# 1-Schematic_testflight2_pcb.net
KiCad netlist of a schematic drawn in EasyEDA
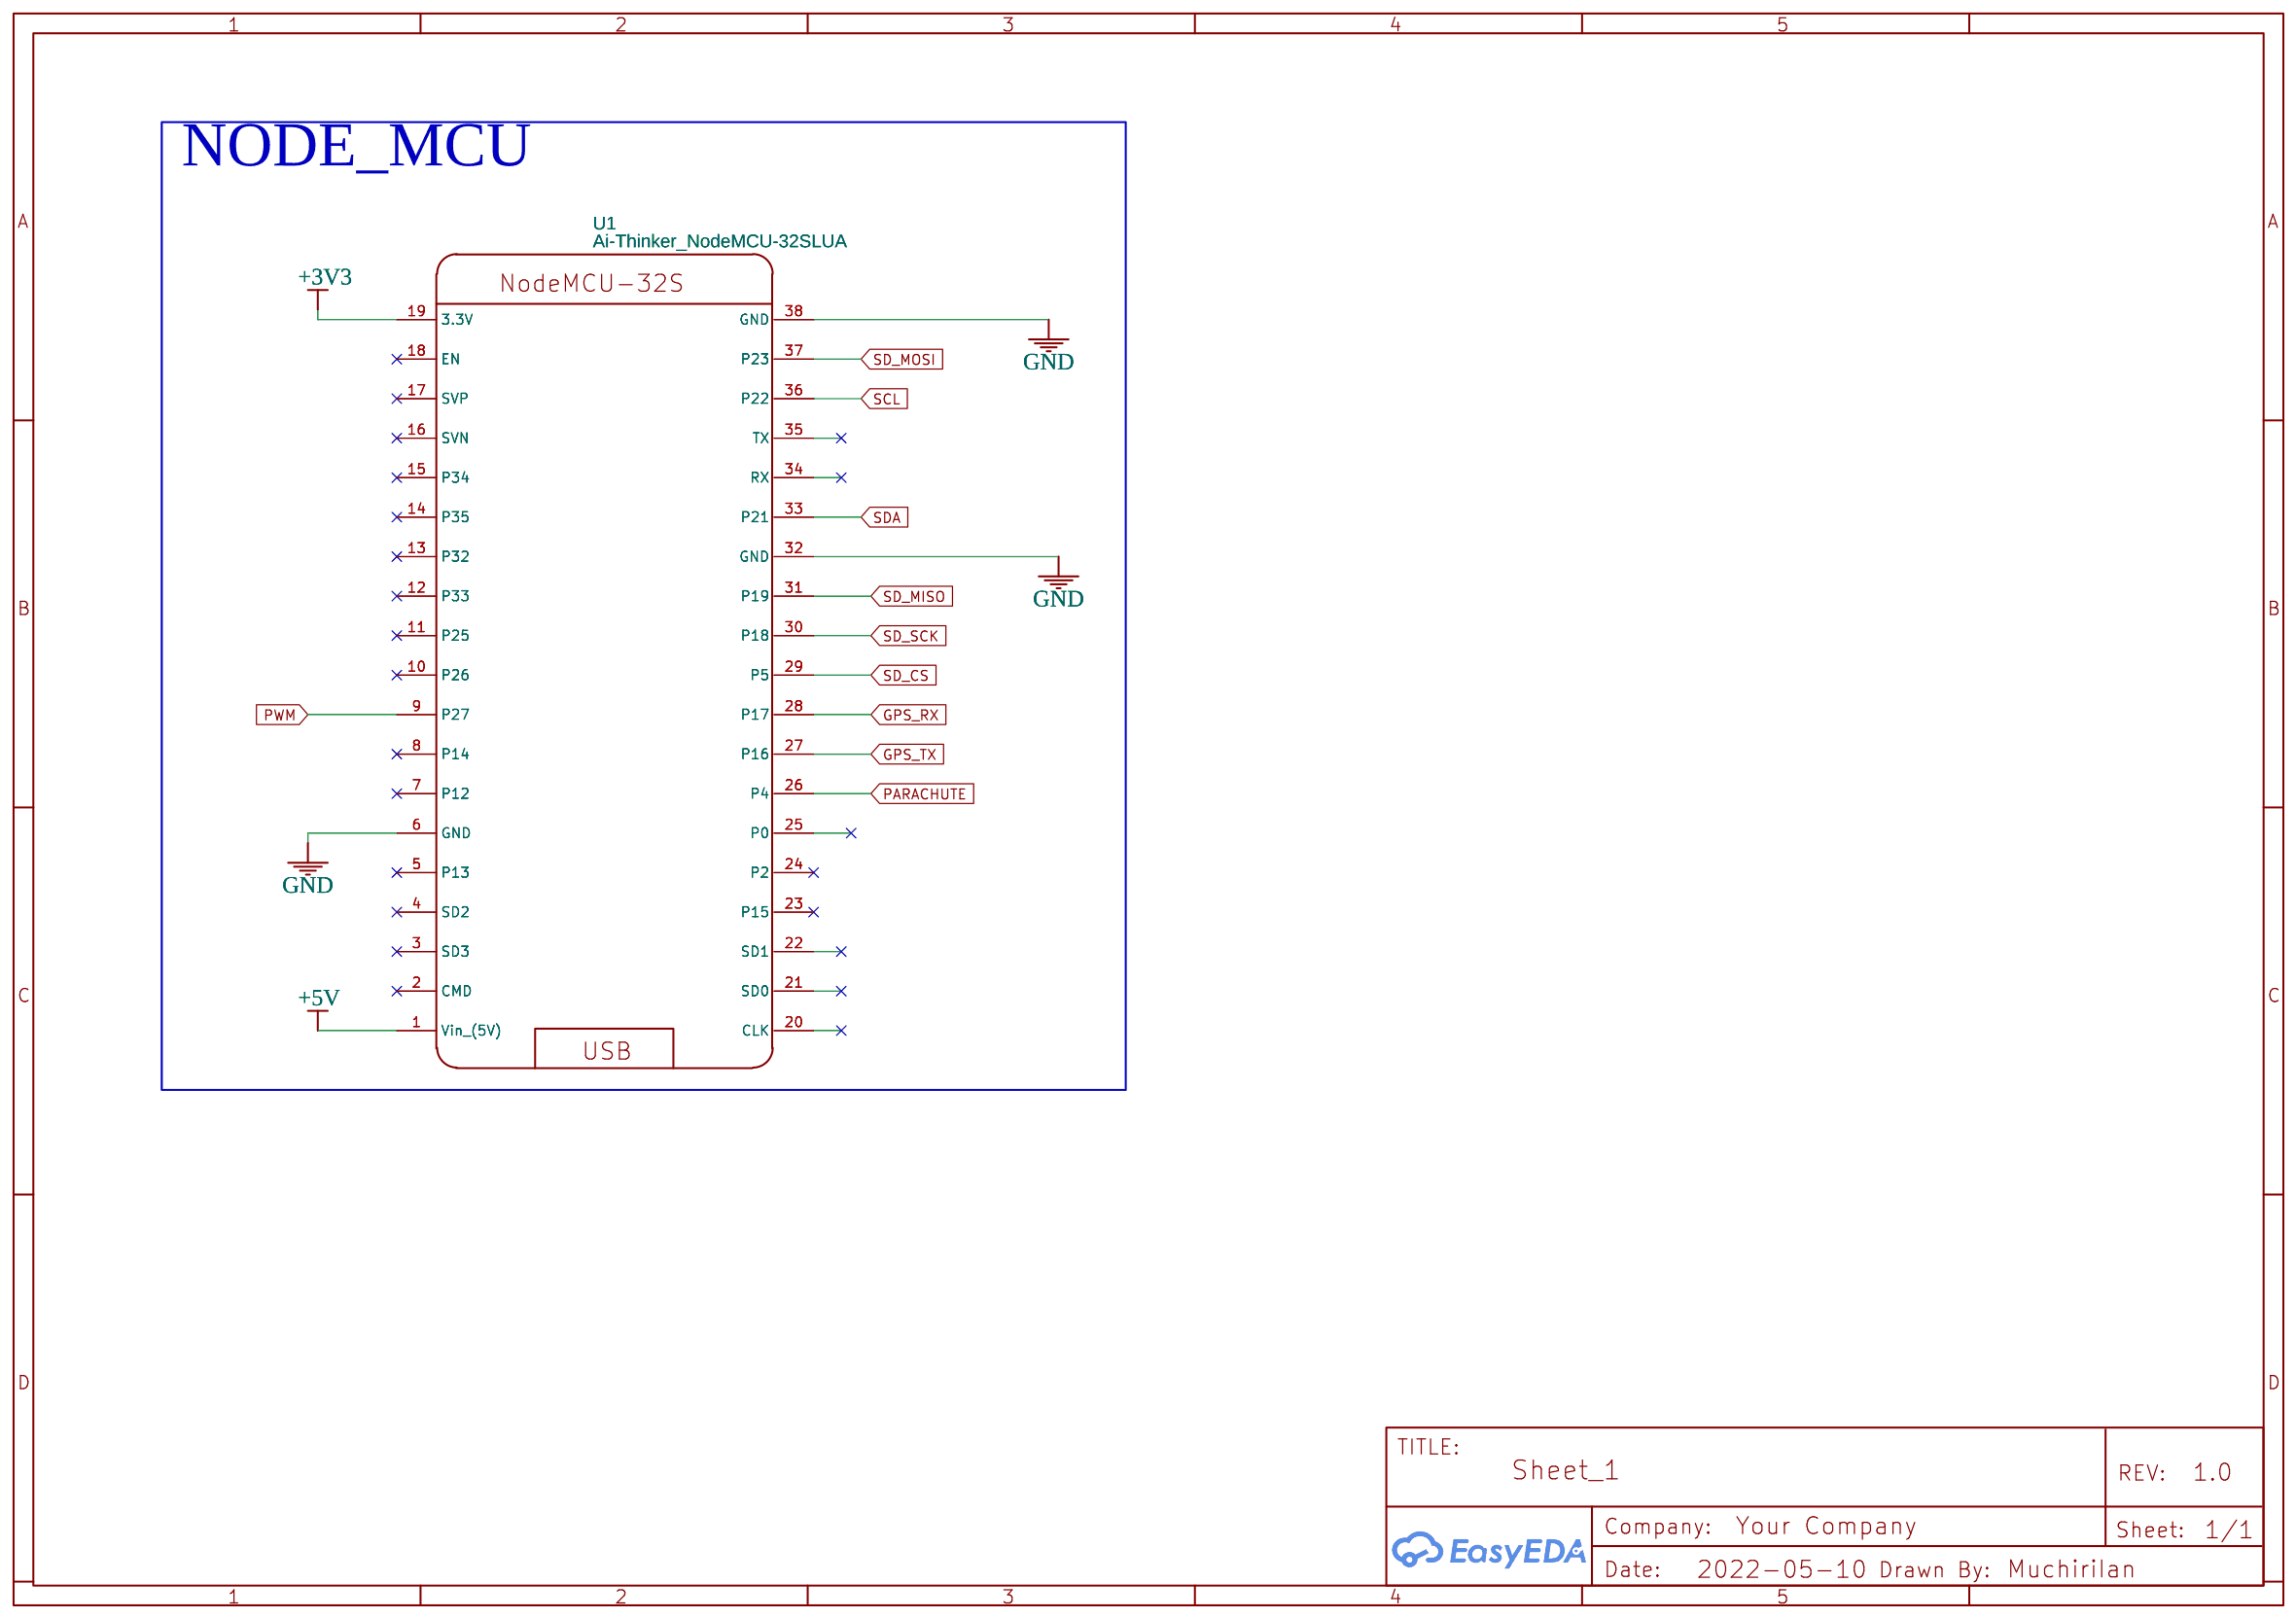
[diagram p0: Sheet_1]
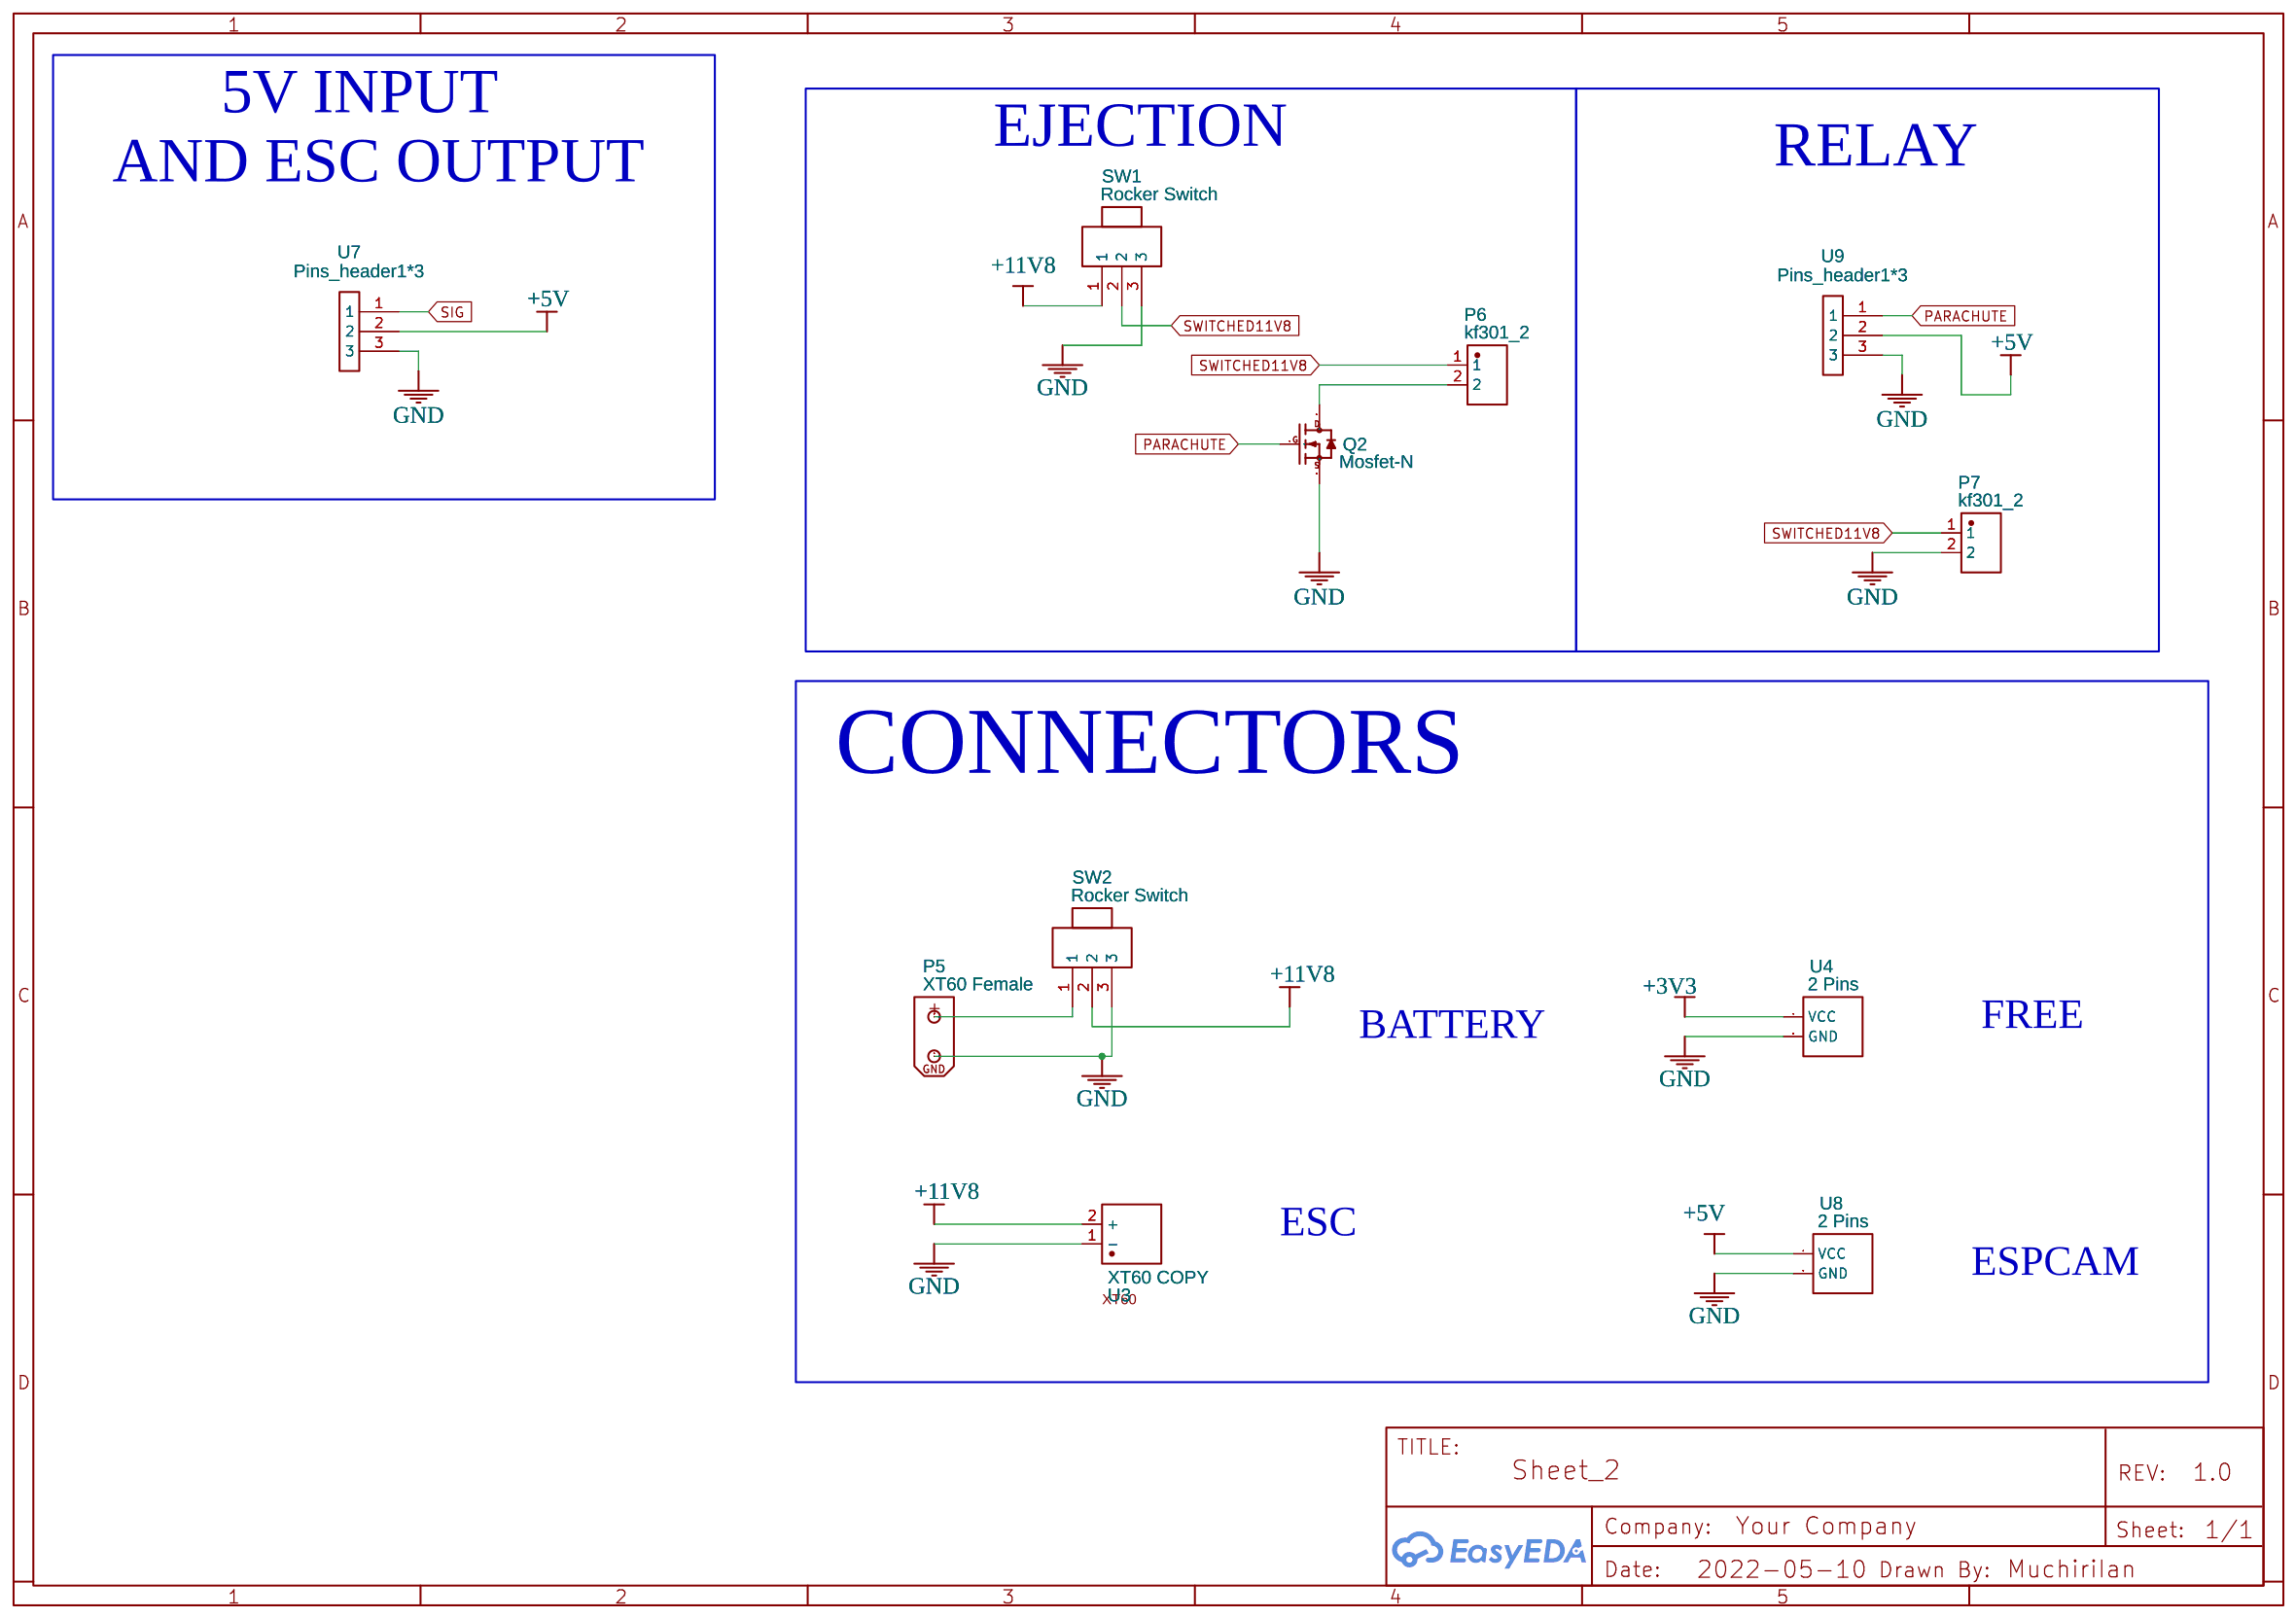
[diagram p1: Sheet_2]
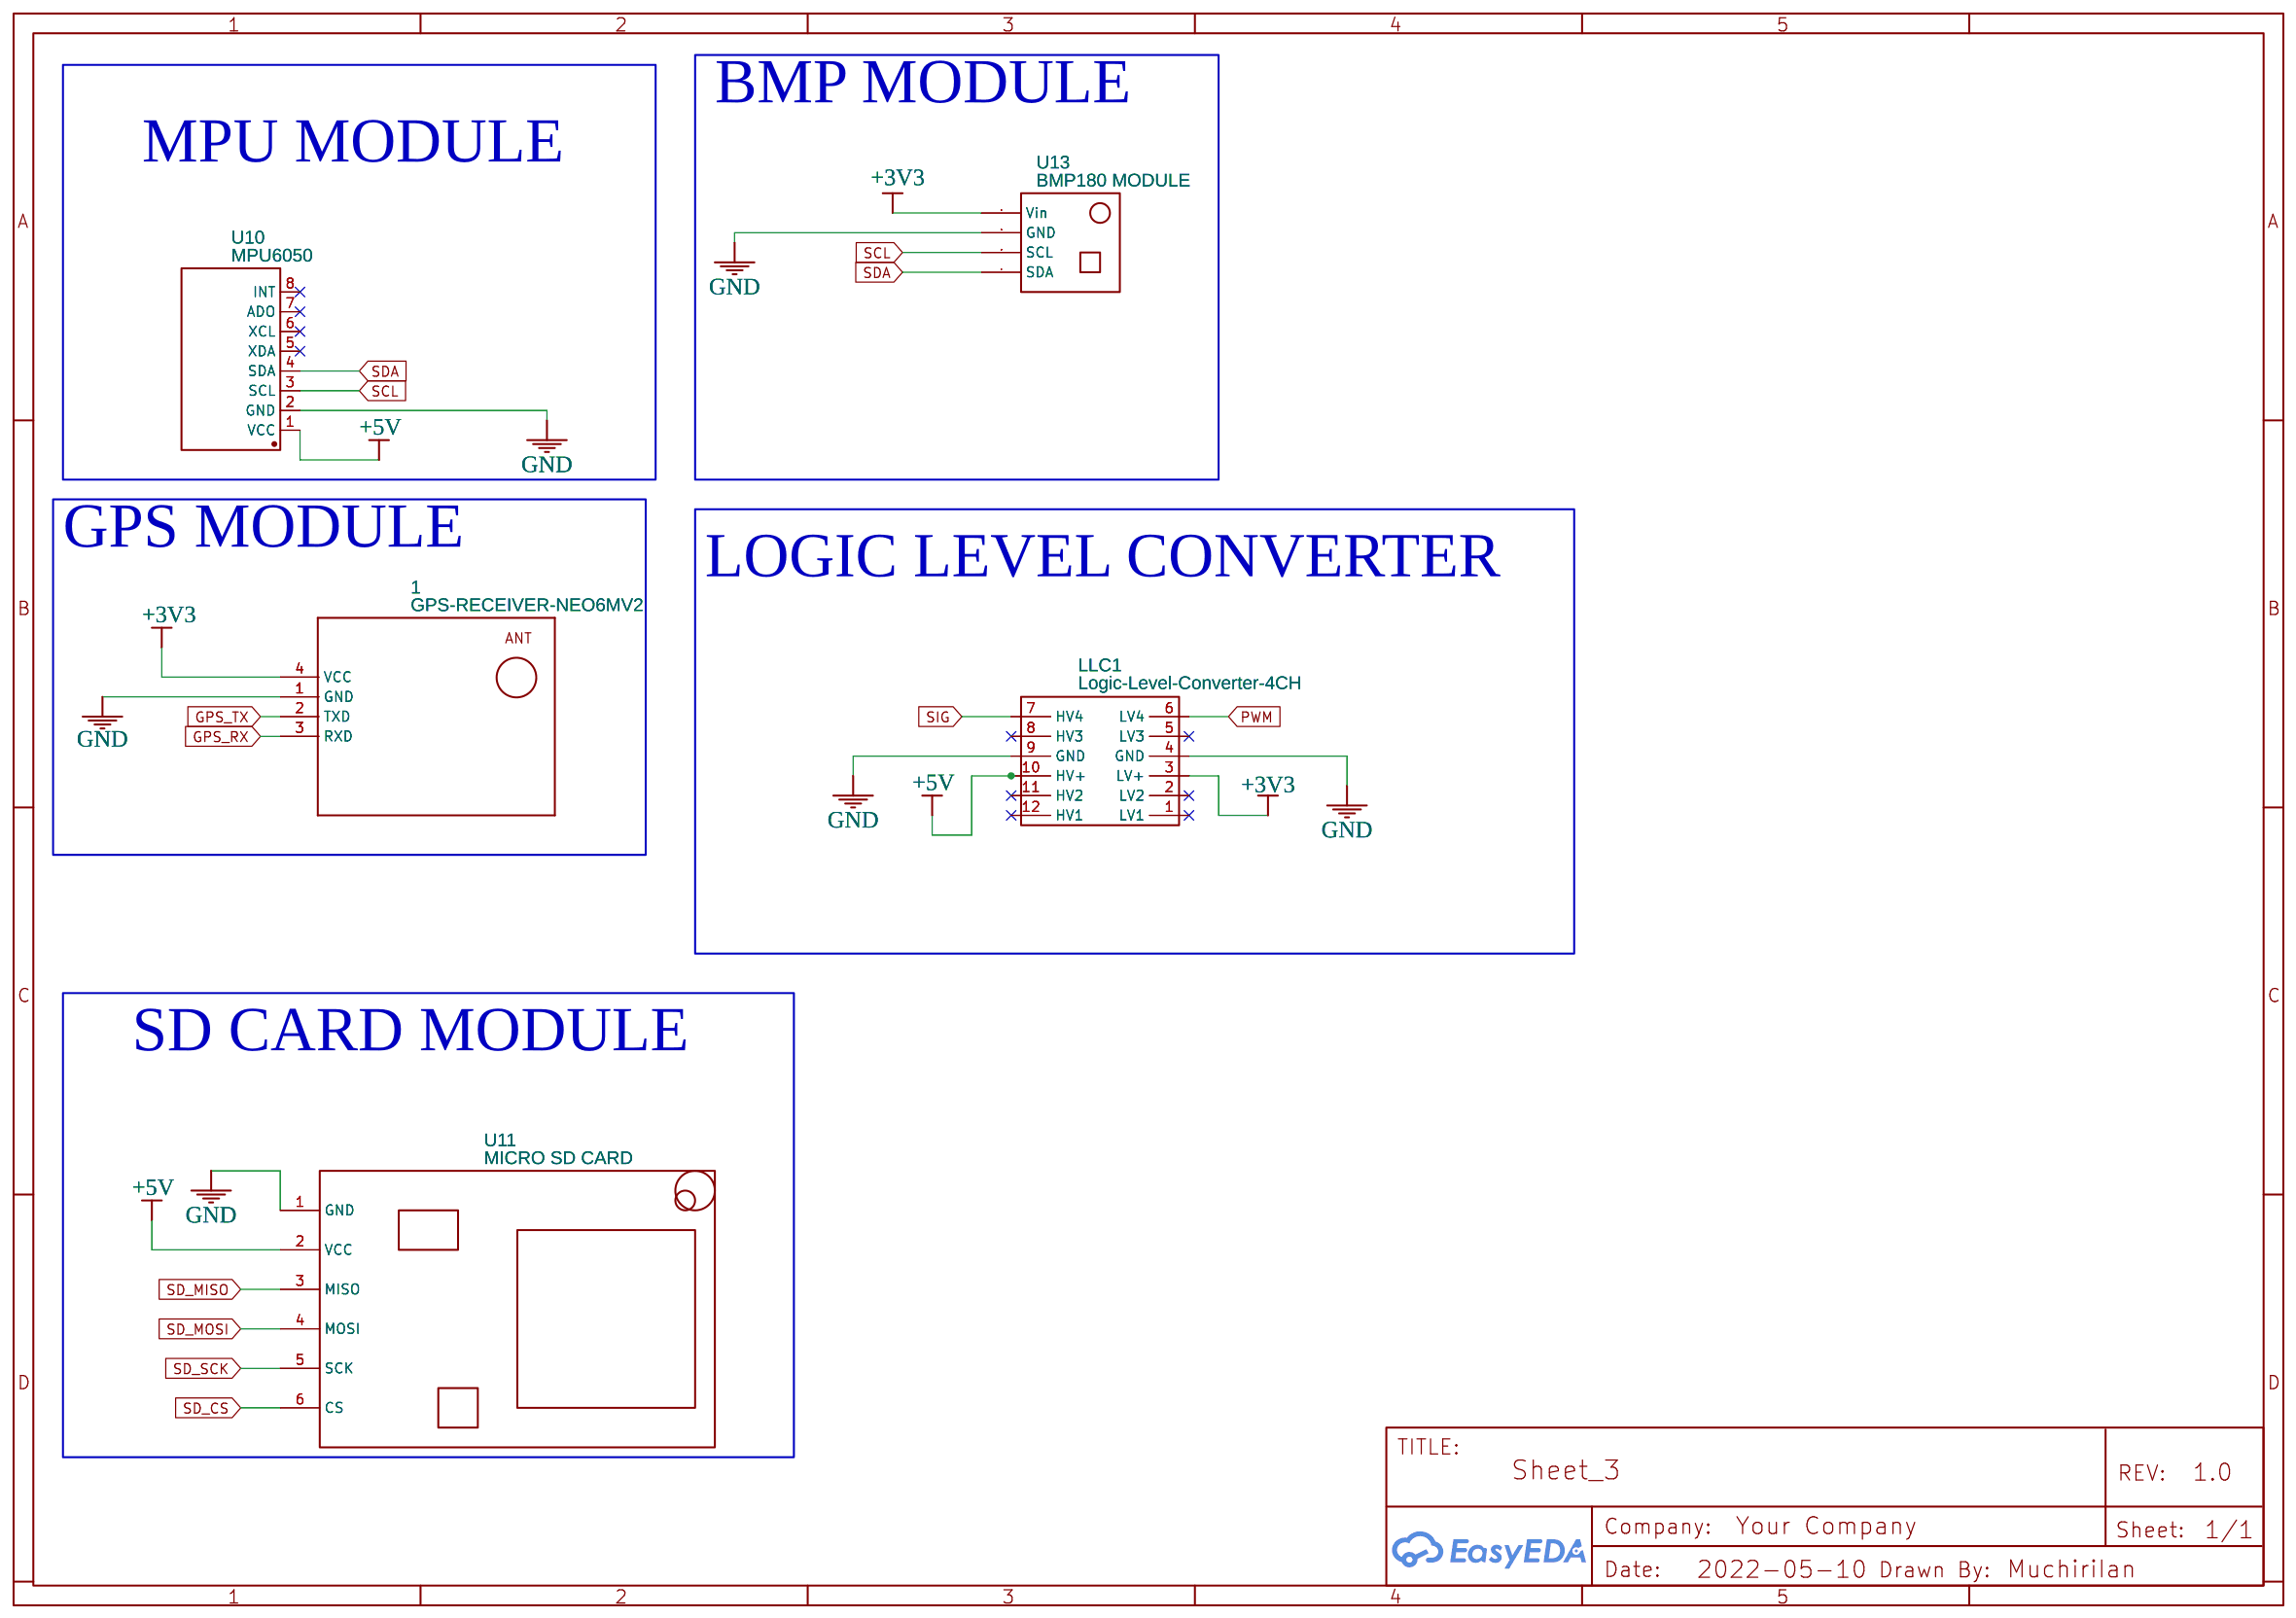
[diagram p2: Sheet_3]

(export (version "E")
  (design (tool "Eeschema 10.0.6"))
  (components
    (comp (ref "U1")
      (value "Ai-Thinker_NodeMCU-32SLUA")
      (fields
        (field (name "BOM_Manufacturer Part") "NodeMCU-32SLua")
        (field (name "BOM_Supplier Part") "C111436")
      )
      (libsource (lib "") (part "Ai-Thinker_NodeMCU-32SLUA"))
    )
    (comp (ref "P5")
      (value "XT60 Female")
      (fields (field (name "BOM_Manufacturer Part") "XT60-F"))
      (libsource (lib "") (part "XT60 Female"))
    )
    (comp (ref "P6")
      (value "kf301_2")
      (fields (field (name "BOM_Supplier Part") "C33435"))
      (libsource (lib "") (part "kf301_2"))
    )
    (comp (ref "P7")
      (value "kf301_2")
      (fields (field (name "BOM_Supplier Part") "C33435"))
      (libsource (lib "") (part "kf301_2"))
    )
    (comp (ref "Q2") (value "Mosfet-N") (libsource (lib "") (part "Mosfet-N")))
    (comp (ref "SW1") (value "Rocker Switch") (libsource (lib "") (part "Rocker Switch")))
    (comp (ref "SW2") (value "Rocker Switch") (libsource (lib "") (part "Rocker Switch")))
    (comp (ref "U3") (value "XT60 COPY") (libsource (lib "") (part "XT60 COPY")))
    (comp (ref "U4") (value "2 Pins") (libsource (lib "") (part "2 Pins")))
    (comp (ref "U7") (value "Pins_header1*3") (libsource (lib "") (part "Pins_header1*3")))
    (comp (ref "U8") (value "2 Pins") (libsource (lib "") (part "2 Pins")))
    (comp (ref "U9") (value "Pins_header1*3") (libsource (lib "") (part "Pins_header1*3")))
    (comp (ref "1") (value "GPS-RECEIVER-NEO6MV2") (libsource (lib "") (part "GPS-RECEIVER-NEO6MV2")))
    (comp (ref "LLC1")
      (value "Logic-Level-Converter-4CH")
      (fields (field (name "BOM_Supplier Part") "50807"))
      (libsource (lib "") (part "Logic-Level-Converter-4CH"))
    )
    (comp (ref "U10")
      (value "MPU6050")
      (fields (field (name "BOM_Supplier Part") "GY521"))
      (libsource (lib "") (part "MPU6050"))
    )
    (comp (ref "U11") (value "MICRO SD CARD") (libsource (lib "") (part "MICRO SD CARD")))
    (comp (ref "U13")
      (value "BMP180 MODULE")
      (fields (field (name "BOM_Manufacturer Part") "BMP180 (HW-596)"))
      (libsource (lib "") (part "BMP180 MODULE"))
    )
  )
  (nets
    (net (code "1") (name "+3V3") (class "Default")
      (node (ref "1") (pin "4") (pinfunction "VCC_4") (pintype "bidirectional"))
      (node (ref "LLC1") (pin "3") (pinfunction "LV+_3") (pintype "unspecified"))
      (node (ref "U1") (pin "19") (pinfunction "3.3V_19") (pintype "unspecified"))
      (node (ref "U13") (pin "1") (pinfunction "Vin_1") (pintype "unspecified"))
      (node (ref "U4") (pin "1") (pinfunction "VCC_1") (pintype "unspecified"))
    )
    (net (code "2") (name "+5V") (class "Default")
      (node (ref "LLC1") (pin "10") (pinfunction "HV+_10") (pintype "unspecified"))
      (node (ref "U1") (pin "1") (pinfunction "Vin_(5V)_1") (pintype "unspecified"))
      (node (ref "U10") (pin "1") (pinfunction "VCC_1") (pintype "unspecified"))
      (node (ref "U11") (pin "2") (pinfunction "VCC_2") (pintype "unspecified"))
      (node (ref "U7") (pin "2") (pinfunction "2_2") (pintype "unspecified"))
      (node (ref "U8") (pin "1") (pinfunction "VCC_1") (pintype "unspecified"))
      (node (ref "U9") (pin "2") (pinfunction "2_2") (pintype "unspecified"))
    )
    (net (code "3") (name "+11V8") (class "Default")
      (node (ref "SW1") (pin "1") (pinfunction "1_1") (pintype "unspecified"))
      (node (ref "SW2") (pin "2") (pinfunction "2_2") (pintype "unspecified"))
      (node (ref "U3") (pin "2") (pinfunction "+_2") (pintype "unspecified"))
    )
    (net (code "4") (name "GND") (class "Default")
      (node (ref "1") (pin "1") (pinfunction "GND_1") (pintype "bidirectional"))
      (node (ref "LLC1") (pin "4") (pinfunction "GND_4") (pintype "unspecified"))
      (node (ref "LLC1") (pin "9") (pinfunction "GND_9") (pintype "unspecified"))
      (node (ref "P5") (pin "1") (pinfunction "1_1") (pintype "unspecified"))
      (node (ref "P7") (pin "2") (pinfunction "2_2") (pintype "unspecified"))
      (node (ref "Q2") (pin "3") (pinfunction "S_3") (pintype "unspecified"))
      (node (ref "SW1") (pin "3") (pinfunction "3_3") (pintype "unspecified"))
      (node (ref "SW2") (pin "3") (pinfunction "3_3") (pintype "unspecified"))
      (node (ref "U1") (pin "32") (pinfunction "GND_32") (pintype "unspecified"))
      (node (ref "U1") (pin "38") (pinfunction "GND_38") (pintype "unspecified"))
      (node (ref "U1") (pin "6") (pinfunction "GND_6") (pintype "unspecified"))
      (node (ref "U10") (pin "2") (pinfunction "GND_2") (pintype "unspecified"))
      (node (ref "U11") (pin "1") (pinfunction "GND_1") (pintype "unspecified"))
      (node (ref "U13") (pin "2") (pinfunction "GND_2") (pintype "unspecified"))
      (node (ref "U3") (pin "1") (pinfunction "-_1") (pintype "unspecified"))
      (node (ref "U4") (pin "2") (pinfunction "GND_2") (pintype "unspecified"))
      (node (ref "U7") (pin "3") (pinfunction "3_3") (pintype "unspecified"))
      (node (ref "U8") (pin "2") (pinfunction "GND_2") (pintype "unspecified"))
      (node (ref "U9") (pin "3") (pinfunction "3_3") (pintype "unspecified"))
    )
    (net (code "5") (name "GPS_RX") (class "Default")
      (node (ref "1") (pin "3") (pinfunction "RXD_3") (pintype "bidirectional"))
      (node (ref "U1") (pin "28") (pinfunction "P17_28") (pintype "unspecified"))
    )
    (net (code "6") (name "GPS_TX") (class "Default")
      (node (ref "1") (pin "2") (pinfunction "TXD_2") (pintype "bidirectional"))
      (node (ref "U1") (pin "27") (pinfunction "P16_27") (pintype "unspecified"))
    )
    (net (code "7") (name "Net-(P5-Pad2)") (class "Default")
      (node (ref "P5") (pin "2") (pinfunction "2_2") (pintype "unspecified"))
      (node (ref "SW2") (pin "1") (pinfunction "1_1") (pintype "unspecified"))
    )
    (net (code "8") (name "Net-(Q2-D)") (class "Default")
      (node (ref "P6") (pin "2") (pinfunction "2_2") (pintype "unspecified"))
      (node (ref "Q2") (pin "2") (pinfunction "D_2") (pintype "unspecified"))
    )
    (net (code "9") (name "PARACHUTE") (class "Default")
      (node (ref "Q2") (pin "1") (pinfunction "G_1") (pintype "unspecified"))
      (node (ref "U1") (pin "26") (pinfunction "P4_26") (pintype "unspecified"))
      (node (ref "U9") (pin "1") (pinfunction "1_1") (pintype "unspecified"))
    )
    (net (code "10") (name "PWM") (class "Default")
      (node (ref "LLC1") (pin "6") (pinfunction "LV4_6") (pintype "unspecified"))
      (node (ref "U1") (pin "9") (pinfunction "P27_9") (pintype "unspecified"))
    )
    (net (code "11") (name "SCL") (class "Default")
      (node (ref "U1") (pin "36") (pinfunction "P22_36") (pintype "unspecified"))
      (node (ref "U10") (pin "3") (pinfunction "SCL_3") (pintype "unspecified"))
      (node (ref "U13") (pin "3") (pinfunction "SCL_3") (pintype "unspecified"))
    )
    (net (code "12") (name "SDA") (class "Default")
      (node (ref "U1") (pin "33") (pinfunction "P21_33") (pintype "unspecified"))
      (node (ref "U10") (pin "4") (pinfunction "SDA_4") (pintype "unspecified"))
      (node (ref "U13") (pin "4") (pinfunction "SDA_4") (pintype "unspecified"))
    )
    (net (code "13") (name "SD_CS") (class "Default")
      (node (ref "U1") (pin "29") (pinfunction "P5_29") (pintype "unspecified"))
      (node (ref "U11") (pin "6") (pinfunction "CS_6") (pintype "unspecified"))
    )
    (net (code "14") (name "SD_MISO") (class "Default")
      (node (ref "U1") (pin "31") (pinfunction "P19_31") (pintype "unspecified"))
      (node (ref "U11") (pin "3") (pinfunction "MISO_3") (pintype "unspecified"))
    )
    (net (code "15") (name "SD_MOSI") (class "Default")
      (node (ref "U1") (pin "37") (pinfunction "P23_37") (pintype "unspecified"))
      (node (ref "U11") (pin "4") (pinfunction "MOSI_4") (pintype "unspecified"))
    )
    (net (code "16") (name "SD_SCK") (class "Default")
      (node (ref "U1") (pin "30") (pinfunction "P18_30") (pintype "unspecified"))
      (node (ref "U11") (pin "5") (pinfunction "SCK_5") (pintype "unspecified"))
    )
    (net (code "17") (name "SIG") (class "Default")
      (node (ref "LLC1") (pin "7") (pinfunction "HV4_7") (pintype "unspecified"))
      (node (ref "U7") (pin "1") (pinfunction "1_1") (pintype "unspecified"))
    )
    (net (code "18") (name "SWITCHED11V8") (class "Default")
      (node (ref "P6") (pin "1") (pinfunction "1_1") (pintype "unspecified"))
      (node (ref "P7") (pin "1") (pinfunction "1_1") (pintype "unspecified"))
      (node (ref "SW1") (pin "2") (pinfunction "2_2") (pintype "unspecified"))
    )
    (net (code "19") (name "unconnected-(LLC1-HV1-Pad12)") (class "Default")
      (node (ref "LLC1") (pin "12") (pinfunction "HV1_12") (pintype "unspecified+no_connect"))
    )
    (net (code "20") (name "unconnected-(LLC1-HV2-Pad11)") (class "Default")
      (node (ref "LLC1") (pin "11") (pinfunction "HV2_11") (pintype "unspecified+no_connect"))
    )
    (net (code "21") (name "unconnected-(LLC1-HV3-Pad8)") (class "Default")
      (node (ref "LLC1") (pin "8") (pinfunction "HV3_8") (pintype "unspecified+no_connect"))
    )
    (net (code "22") (name "unconnected-(LLC1-LV1-Pad1)") (class "Default")
      (node (ref "LLC1") (pin "1") (pinfunction "LV1_1") (pintype "unspecified+no_connect"))
    )
    (net (code "23") (name "unconnected-(LLC1-LV2-Pad2)") (class "Default")
      (node (ref "LLC1") (pin "2") (pinfunction "LV2_2") (pintype "unspecified+no_connect"))
    )
    (net (code "24") (name "unconnected-(LLC1-LV3-Pad5)") (class "Default")
      (node (ref "LLC1") (pin "5") (pinfunction "LV3_5") (pintype "unspecified+no_connect"))
    )
    (net (code "25") (name "unconnected-(U1-CLK-Pad20)") (class "Default")
      (node (ref "U1") (pin "20") (pinfunction "CLK_20") (pintype "unspecified+no_connect"))
    )
    (net (code "26") (name "unconnected-(U1-CMD-Pad2)") (class "Default")
      (node (ref "U1") (pin "2") (pinfunction "CMD_2") (pintype "unspecified+no_connect"))
    )
    (net (code "27") (name "unconnected-(U1-EN-Pad18)") (class "Default")
      (node (ref "U1") (pin "18") (pinfunction "EN_18") (pintype "unspecified+no_connect"))
    )
    (net (code "28") (name "unconnected-(U1-P0-Pad25)") (class "Default")
      (node (ref "U1") (pin "25") (pinfunction "P0_25") (pintype "unspecified+no_connect"))
    )
    (net (code "29") (name "unconnected-(U1-P2-Pad24)") (class "Default")
      (node (ref "U1") (pin "24") (pinfunction "P2_24") (pintype "unspecified+no_connect"))
    )
    (net (code "30") (name "unconnected-(U1-P12-Pad7)") (class "Default")
      (node (ref "U1") (pin "7") (pinfunction "P12_7") (pintype "unspecified+no_connect"))
    )
    (net (code "31") (name "unconnected-(U1-P13-Pad5)") (class "Default")
      (node (ref "U1") (pin "5") (pinfunction "P13_5") (pintype "unspecified+no_connect"))
    )
    (net (code "32") (name "unconnected-(U1-P14-Pad8)") (class "Default")
      (node (ref "U1") (pin "8") (pinfunction "P14_8") (pintype "unspecified+no_connect"))
    )
    (net (code "33") (name "unconnected-(U1-P15-Pad23)") (class "Default")
      (node (ref "U1") (pin "23") (pinfunction "P15_23") (pintype "unspecified+no_connect"))
    )
    (net (code "34") (name "unconnected-(U1-P25-Pad11)") (class "Default")
      (node (ref "U1") (pin "11") (pinfunction "P25_11") (pintype "unspecified+no_connect"))
    )
    (net (code "35") (name "unconnected-(U1-P26-Pad10)") (class "Default")
      (node (ref "U1") (pin "10") (pinfunction "P26_10") (pintype "unspecified+no_connect"))
    )
    (net (code "36") (name "unconnected-(U1-P32-Pad13)") (class "Default")
      (node (ref "U1") (pin "13") (pinfunction "P32_13") (pintype "unspecified+no_connect"))
    )
    (net (code "37") (name "unconnected-(U1-P33-Pad12)") (class "Default")
      (node (ref "U1") (pin "12") (pinfunction "P33_12") (pintype "unspecified+no_connect"))
    )
    (net (code "38") (name "unconnected-(U1-P34-Pad15)") (class "Default")
      (node (ref "U1") (pin "15") (pinfunction "P34_15") (pintype "unspecified+no_connect"))
    )
    (net (code "39") (name "unconnected-(U1-P35-Pad14)") (class "Default")
      (node (ref "U1") (pin "14") (pinfunction "P35_14") (pintype "unspecified+no_connect"))
    )
    (net (code "40") (name "unconnected-(U1-RX-Pad34)") (class "Default")
      (node (ref "U1") (pin "34") (pinfunction "RX_34") (pintype "unspecified+no_connect"))
    )
    (net (code "41") (name "unconnected-(U1-SD0-Pad21)") (class "Default")
      (node (ref "U1") (pin "21") (pinfunction "SD0_21") (pintype "unspecified+no_connect"))
    )
    (net (code "42") (name "unconnected-(U1-SD1-Pad22)") (class "Default")
      (node (ref "U1") (pin "22") (pinfunction "SD1_22") (pintype "unspecified+no_connect"))
    )
    (net (code "43") (name "unconnected-(U1-SD2-Pad4)") (class "Default")
      (node (ref "U1") (pin "4") (pinfunction "SD2_4") (pintype "unspecified+no_connect"))
    )
    (net (code "44") (name "unconnected-(U1-SD3-Pad3)") (class "Default")
      (node (ref "U1") (pin "3") (pinfunction "SD3_3") (pintype "unspecified+no_connect"))
    )
    (net (code "45") (name "unconnected-(U1-SVN-Pad16)") (class "Default")
      (node (ref "U1") (pin "16") (pinfunction "SVN_16") (pintype "unspecified+no_connect"))
    )
    (net (code "46") (name "unconnected-(U1-SVP-Pad17)") (class "Default")
      (node (ref "U1") (pin "17") (pinfunction "SVP_17") (pintype "unspecified+no_connect"))
    )
    (net (code "47") (name "unconnected-(U1-TX-Pad35)") (class "Default")
      (node (ref "U1") (pin "35") (pinfunction "TX_35") (pintype "unspecified+no_connect"))
    )
    (net (code "48") (name "unconnected-(U10-ADO-Pad7)") (class "Default")
      (node (ref "U10") (pin "7") (pinfunction "ADO_7") (pintype "unspecified+no_connect"))
    )
    (net (code "49") (name "unconnected-(U10-INT-Pad8)") (class "Default")
      (node (ref "U10") (pin "8") (pinfunction "INT_8") (pintype "unspecified+no_connect"))
    )
    (net (code "50") (name "unconnected-(U10-XCL-Pad6)") (class "Default")
      (node (ref "U10") (pin "6") (pinfunction "XCL_6") (pintype "unspecified+no_connect"))
    )
    (net (code "51") (name "unconnected-(U10-XDA-Pad5)") (class "Default")
      (node (ref "U10") (pin "5") (pinfunction "XDA_5") (pintype "unspecified+no_connect"))
    )
  )
)
